# servo-controller.net
KiCad netlist of a schematic drawn in EAGLE
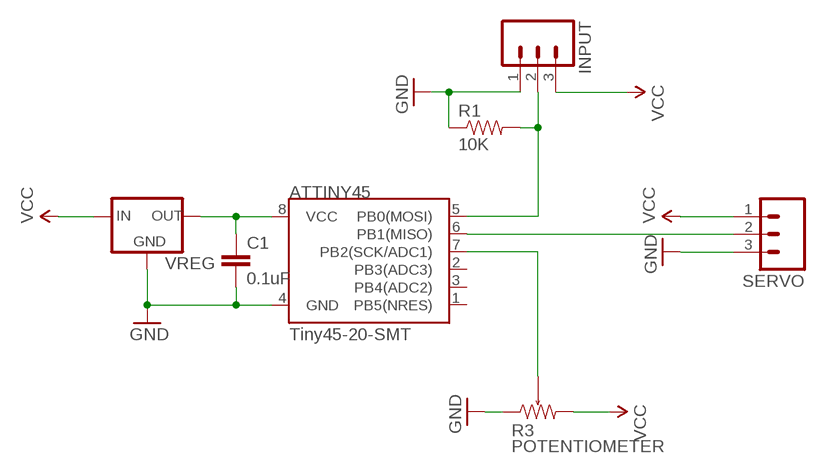
[diagram p0: schematic, sheet 1]

(export (version "E")
  (design (tool "Eeschema 10.0.6"))
  (components
    (comp (ref "ATTINY45")
      (value "Tiny45-20-SMT")
      (footprint "eagle-import:SO08-EIAJ")
      (libsource (lib "eagle-import") (part "ATTINY45TINY45-20-SMT"))
    )
    (comp (ref "C1")
      (value "0.1uF")
      (footprint "eagle-import:0603-CAP")
      (libsource (lib "eagle-import") (part "0.1UF-25V-5%(0603)"))
    )
    (comp (ref "INPUT")
      (value "M03PTH")
      (footprint "eagle-import:1X03")
      (libsource (lib "eagle-import") (part "M03PTH"))
    )
    (comp (ref "R1")
      (value "10K")
      (footprint "eagle-import:0603-RES")
      (libsource (lib "eagle-import") (part "10KOHM-1/10W-1%(0603)0603"))
    )
    (comp (ref "R3")
      (value "POTENTIOMETER")
      (footprint "eagle-import:0603-ARV")
      (libsource (lib "eagle-import") (part "POTENTIOMETER"))
    )
    (comp (ref "SERVO")
      (value "M03PTH")
      (footprint "eagle-import:1X03")
      (libsource (lib "eagle-import") (part "M03PTH"))
    )
    (comp (ref "VREG")
      (value "V_REG_78XX-TO-220")
      (footprint "eagle-import:TO-220-ALT")
      (libsource (lib "eagle-import") (part "V_REG_78XX-TO-220"))
    )
  )
  (nets
    (net (code "1") (name "GND") (class "Default")
      (node (ref "ATTINY45") (pin "4") (pinfunction "GND_4") (pintype "bidirectional"))
      (node (ref "C1") (pin "2") (pinfunction "2_2") (pintype "passive"))
      (node (ref "INPUT") (pin "1") (pinfunction "1_1") (pintype "passive"))
      (node (ref "R1") (pin "1") (pinfunction "1_1") (pintype "passive"))
      (node (ref "R3") (pin "1") (pinfunction "1_1") (pintype "passive"))
      (node (ref "SERVO") (pin "3") (pinfunction "3_3") (pintype "passive"))
      (node (ref "VREG") (pin "GND") (pinfunction "GND_GND") (pintype "input"))
    )
    (net (code "2") (name "Net-(ATTINY45-PB0(MOSI))") (class "Default")
      (node (ref "ATTINY45") (pin "5") (pinfunction "PB0(MOSI)_5") (pintype "bidirectional"))
      (node (ref "INPUT") (pin "2") (pinfunction "2_2") (pintype "passive"))
      (node (ref "R1") (pin "2") (pinfunction "2_2") (pintype "passive"))
    )
    (net (code "3") (name "Net-(ATTINY45-PB1(MISO))") (class "Default")
      (node (ref "ATTINY45") (pin "6") (pinfunction "PB1(MISO)_6") (pintype "bidirectional"))
      (node (ref "SERVO") (pin "2") (pinfunction "2_2") (pintype "passive"))
    )
    (net (code "4") (name "Net-(ATTINY45-PB2(SCK{slash}ADC1))") (class "Default")
      (node (ref "ATTINY45") (pin "7") (pinfunction "PB2(SCK/ADC1)_7") (pintype "bidirectional"))
      (node (ref "R3") (pin "3") (pinfunction "P$1_3") (pintype "bidirectional"))
      (node (ref "R3") (pin "4") (pinfunction "P$1_4") (pintype "bidirectional"))
      (node (ref "R3") (pin "5") (pinfunction "P$1_5") (pintype "bidirectional"))
      (node (ref "R3") (pin "6") (pinfunction "P$1_6") (pintype "bidirectional"))
      (node (ref "R3") (pin "7") (pinfunction "P$1_7") (pintype "bidirectional"))
      (node (ref "R3") (pin "8") (pinfunction "P$1_8") (pintype "bidirectional"))
    )
    (net (code "5") (name "Net-(ATTINY45-VCC)") (class "Default")
      (node (ref "ATTINY45") (pin "8") (pinfunction "VCC_8") (pintype "bidirectional"))
      (node (ref "C1") (pin "1") (pinfunction "1_1") (pintype "passive"))
      (node (ref "VREG") (pin "OUT") (pinfunction "OUT_OUT") (pintype "output"))
    )
    (net (code "6") (name "VCC") (class "Default")
      (node (ref "INPUT") (pin "3") (pinfunction "3_3") (pintype "passive"))
      (node (ref "R3") (pin "2") (pinfunction "2_2") (pintype "passive"))
      (node (ref "SERVO") (pin "1") (pinfunction "1_1") (pintype "passive"))
      (node (ref "VREG") (pin "IN") (pinfunction "IN_IN") (pintype "input"))
    )
    (net (code "7") (name "unconnected-(ATTINY45-PB3(ADC3)-Pad2)") (class "Default")
      (node (ref "ATTINY45") (pin "2") (pinfunction "PB3(ADC3)_2") (pintype "bidirectional"))
    )
    (net (code "8") (name "unconnected-(ATTINY45-PB4(ADC2)-Pad3)") (class "Default")
      (node (ref "ATTINY45") (pin "3") (pinfunction "PB4(ADC2)_3") (pintype "bidirectional"))
    )
    (net (code "9") (name "unconnected-(ATTINY45-PB5(NRES)-Pad1)") (class "Default")
      (node (ref "ATTINY45") (pin "1") (pinfunction "PB5(NRES)_1") (pintype "bidirectional"))
    )
  )
)
